# AstableMultivibrator-PNP-alt2.net
KiCad netlist of a schematic drawn in EAGLE
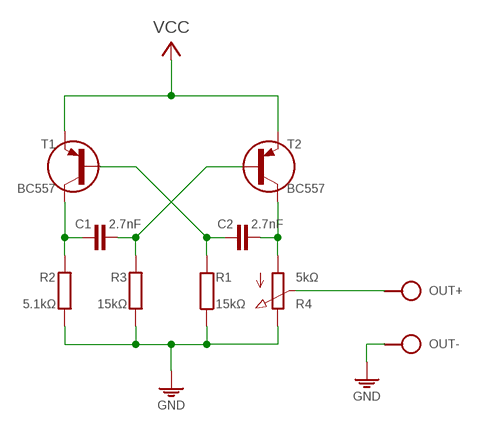
[diagram p0: schematic, sheet 1]

(export (version "E")
  (design (tool "Eeschema 10.0.6"))
  (components
    (comp (ref "C1")
      (value "2.7nF")
      (footprint "eagle-import:C075-020X044")
      (libsource (lib "eagle-import") (part "C-H075-020X044"))
    )
    (comp (ref "C2")
      (value "2.7nF")
      (footprint "eagle-import:C075-020X044")
      (libsource (lib "eagle-import") (part "C-H075-020X044"))
    )
    (comp (ref "J1")
      (value "VCC_GNDPWR-L")
      (footprint "eagle-import:PWR-L")
      (libsource (lib "eagle-import") (part "VCC_GNDPWR-L"))
    )
    (comp (ref "OUT")
      (value "SPAD+--+")
      (footprint "eagle-import:SPAD-+")
      (libsource (lib "eagle-import") (part "SPAD+--+"))
    )
    (comp (ref "R1")
      (value "15kΩ")
      (footprint "eagle-import:0202_7-V")
      (libsource (lib "eagle-import") (part "R0202/7-V"))
    )
    (comp (ref "R2")
      (value "5.1kΩ")
      (footprint "eagle-import:0202_7-V")
      (libsource (lib "eagle-import") (part "R0202/7-V"))
    )
    (comp (ref "R3")
      (value "15kΩ")
      (footprint "eagle-import:0202_7-V")
      (libsource (lib "eagle-import") (part "R0202/7-V"))
    )
    (comp (ref "R4")
      (value "5kΩ")
      (footprint "eagle-import:POT-V")
      (libsource (lib "eagle-import") (part "POT-V"))
    )
    (comp (ref "T1")
      (value "BC557")
      (footprint "eagle-import:TO92-CBE")
      (libsource (lib "eagle-import") (part "BC557CBE"))
    )
    (comp (ref "T2")
      (value "BC557")
      (footprint "eagle-import:TO92-CBE")
      (libsource (lib "eagle-import") (part "BC557CBE"))
    )
  )
  (nets
    (net (code "1") (name "GND") (class "Default")
      (node (ref "J1") (pin "1") (pinfunction "GND_1") (pintype "power_in"))
      (node (ref "OUT") (pin "1") (pinfunction "P$1_1") (pintype "passive"))
      (node (ref "R1") (pin "1") (pinfunction "2_1") (pintype "passive"))
      (node (ref "R2") (pin "1") (pinfunction "2_1") (pintype "passive"))
      (node (ref "R3") (pin "1") (pinfunction "2_1") (pintype "passive"))
      (node (ref "R4") (pin "E") (pinfunction "E_E") (pintype "passive"))
    )
    (net (code "2") (name "Net-(C2-Pad2)") (class "Default")
      (node (ref "C2") (pin "2") (pinfunction "2_2") (pintype "passive"))
      (node (ref "R4") (pin "A") (pinfunction "A_A") (pintype "passive"))
      (node (ref "T2") (pin "C") (pinfunction "C_C") (pintype "passive"))
    )
    (net (code "3") (name "Net-(J1A-VCC)") (class "Default")
      (node (ref "J1") (pin "2") (pinfunction "VCC_2") (pintype "power_in"))
      (node (ref "T1") (pin "E") (pinfunction "E_E") (pintype "passive"))
      (node (ref "T2") (pin "E") (pinfunction "E_E") (pintype "passive"))
    )
    (net (code "4") (name "Net-(OUTA-P$1)") (class "Default")
      (node (ref "OUT") (pin "2") (pinfunction "P$1_2") (pintype "passive"))
      (node (ref "R4") (pin "S") (pinfunction "S_S") (pintype "passive"))
    )
    (net (code "5") (name "Net-(R1-1)") (class "Default")
      (node (ref "C2") (pin "1") (pinfunction "1_1") (pintype "passive"))
      (node (ref "R1") (pin "2") (pinfunction "1_2") (pintype "passive"))
      (node (ref "T1") (pin "B") (pinfunction "B_B") (pintype "passive"))
    )
    (net (code "6") (name "Net-(R2-1)") (class "Default")
      (node (ref "C1") (pin "1") (pinfunction "1_1") (pintype "passive"))
      (node (ref "R2") (pin "2") (pinfunction "1_2") (pintype "passive"))
      (node (ref "T1") (pin "C") (pinfunction "C_C") (pintype "passive"))
    )
    (net (code "7") (name "Net-(R3-1)") (class "Default")
      (node (ref "C1") (pin "2") (pinfunction "2_2") (pintype "passive"))
      (node (ref "R3") (pin "2") (pinfunction "1_2") (pintype "passive"))
      (node (ref "T2") (pin "B") (pinfunction "B_B") (pintype "passive"))
    )
  )
)
